# RS232_485_dsPIC30.net
KiCad netlist of a schematic drawn in Altium Designer
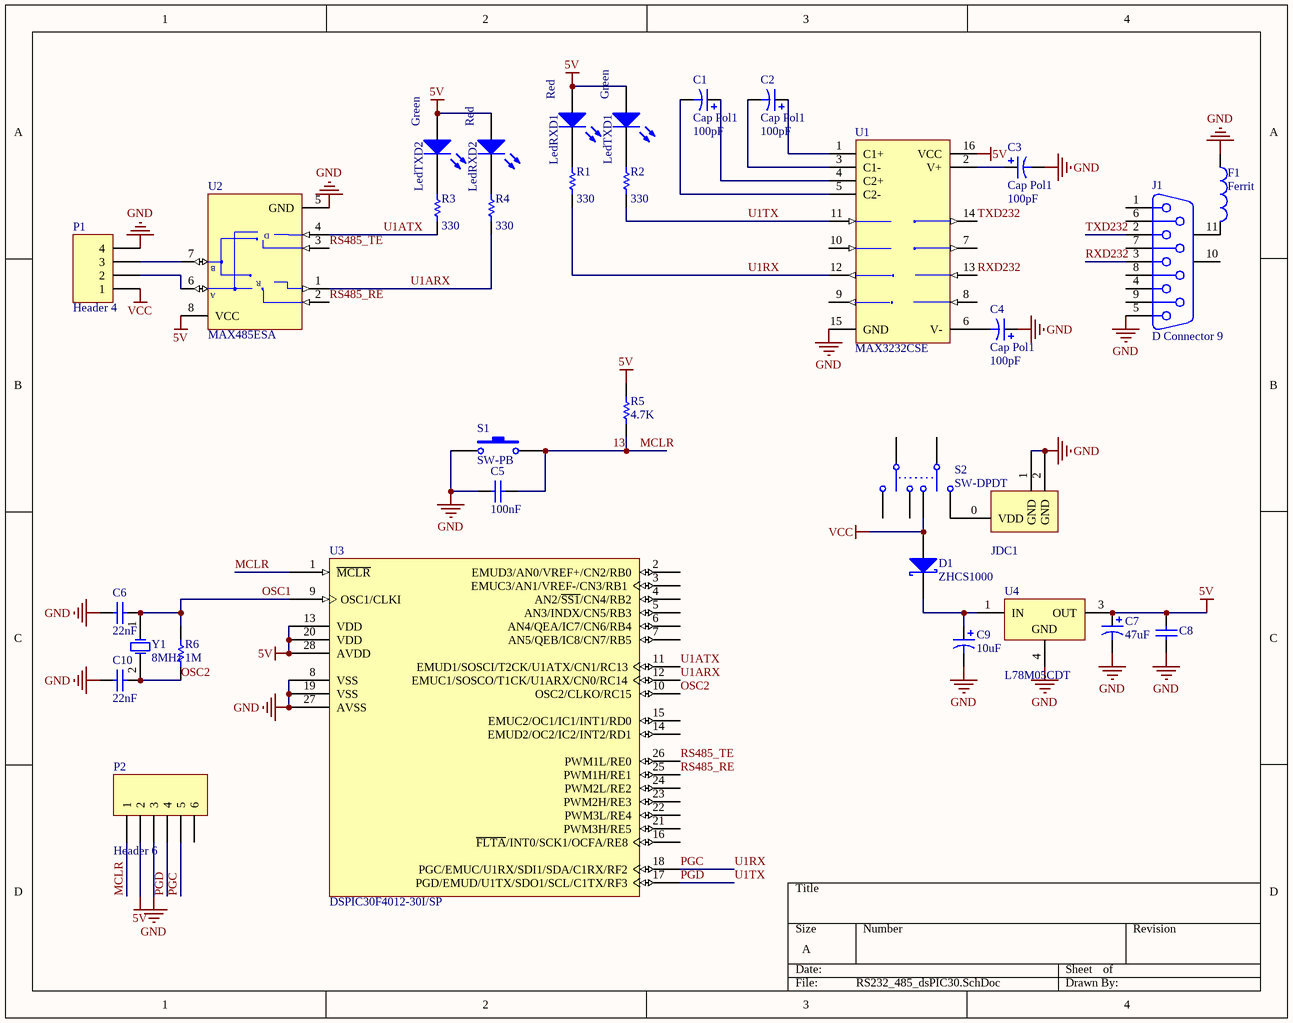
[diagram p0: RS232_485_dsPIC30.SchDoc]

(export (version "E")
  (design (tool "Eeschema 10.0.6"))
  (components
    (comp (ref "C1")
      (value "Cap Pol1")
      (footprint "CAPPR2-5x6.8")
      (description "Polarized Capacitor (Radial)")
      (fields (field (name "ALTIUM_VALUE") "100pF") (field (name "PUBLISHER") "Altium Limited"))
      (libsource (lib "Miscellaneous Devices") (part "Cap Pol1"))
    )
    (comp (ref "C2")
      (value "Cap Pol1")
      (footprint "CAPPR2-5x6.8")
      (description "Polarized Capacitor (Radial)")
      (fields (field (name "ALTIUM_VALUE") "100pF") (field (name "PUBLISHER") "Altium Limited"))
      (libsource (lib "Miscellaneous Devices") (part "Cap Pol1"))
    )
    (comp (ref "C3")
      (value "Cap Pol1")
      (footprint "CAPPR2-5x6.8")
      (description "Polarized Capacitor (Radial)")
      (fields (field (name "ALTIUM_VALUE") "100pF") (field (name "PUBLISHER") "Altium Limited"))
      (libsource (lib "Miscellaneous Devices") (part "Cap Pol1"))
    )
    (comp (ref "C4")
      (value "Cap Pol1")
      (footprint "CAPPR2-5x6.8")
      (description "Polarized Capacitor (Radial)")
      (fields (field (name "ALTIUM_VALUE") "100pF") (field (name "PUBLISHER") "Altium Limited"))
      (libsource (lib "Miscellaneous Devices") (part "Cap Pol1"))
    )
    (comp (ref "C5")
      (value "100nF")
      (footprint "CAPC1608L")
      (description "Capacitor (Semiconductor SIM Model)")
      (fields (field (name "Comment") "Cap Semi") (field (name "PUBLISHER") "Altium Limited"))
      (libsource (lib "Miscellaneous Devices") (part "Cap Semi"))
    )
    (comp (ref "C6")
      (value "22nF")
      (footprint "CAPC1608L")
      (description "Capacitor (Semiconductor SIM Model)")
      (fields (field (name "Comment") "Cap Semi") (field (name "PUBLISHER") "Altium Limited"))
      (libsource (lib "Miscellaneous Devices") (part "Cap Semi"))
    )
    (comp (ref "C7")
      (value "47uF")
      (footprint "CAP4060L")
      (description "Polarized Capacitor (Surface Mount)")
      (fields (field (name "Comment") "Cap Pol3") (field (name "PUBLISHER") "Altium Limited"))
      (libsource (lib "Miscellaneous Devices") (part "Cap Pol3"))
    )
    (comp (ref "C8")
      (value "Cap Semi")
      (footprint "CAPC1608L")
      (description "Capacitor (Semiconductor SIM Model)")
      (fields (field (name "PUBLISHER") "Altium Limited"))
      (libsource (lib "Miscellaneous Devices") (part "Cap Semi"))
    )
    (comp (ref "C9")
      (value "10uF")
      (footprint "CAPC3216L")
      (description "Polarized Capacitor (Surface Mount)")
      (fields (field (name "Comment") "Cap Pol3") (field (name "PUBLISHER") "Altium Limited"))
      (libsource (lib "Miscellaneous Devices") (part "Cap Pol3"))
    )
    (comp (ref "C10")
      (value "22nF")
      (footprint "CAPC1608L")
      (description "Capacitor (Semiconductor SIM Model)")
      (fields (field (name "Comment") "Cap Semi") (field (name "PUBLISHER") "Altium Limited"))
      (libsource (lib "Miscellaneous Devices") (part "Cap Semi"))
    )
    (comp (ref "D1")
      (value "ZHCS1000")
      (footprint "SOT95P240-3N")
      (description "Silicon AF Schottky Diode for High-Speed Switching")
      (fields (field (name "PUBLISHER") "Altium Limited"))
      (libsource (lib "Miscellaneous Devices") (part "Diode BAS70"))
    )
    (comp (ref "F1")
      (value "Ferrit")
      (footprint "INDC2012L")
      (description "Inductor")
      (fields (field (name "PUBLISHER") "Altium Limited"))
      (libsource (lib "Miscellaneous Devices") (part "Inductor"))
    )
    (comp (ref "J1")
      (value "D Connector 9")
      (footprint "DSUB1.385-2H9")
      (description "Receptacle Assembly, 9 Position, Right Angle")
      (fields (field (name "PUBLISHER") "Altium Limited"))
      (libsource (lib "Miscellaneous Connectors") (part "D Connector 9"))
    )
    (comp (ref "JDC1")
      (value "Jac_DC")
      (footprint "Jac_DC_C")
      (libsource (lib "My_Integrated_Library") (part "Jac_DC"))
    )
    (comp (ref "LedRXD1")
      (value "Red")
      (footprint "RESC2012N")
      (description "Typical RED, GREEN, YELLOW, AMBER GaAs LED")
      (fields (field (name "PUBLISHER") "Altium Limited"))
      (libsource (lib "Miscellaneous Devices") (part "LED2"))
    )
    (comp (ref "LedRXD2")
      (value "Red")
      (footprint "RESC2012N")
      (description "Typical RED, GREEN, YELLOW, AMBER GaAs LED")
      (fields (field (name "PUBLISHER") "Altium Limited"))
      (libsource (lib "Miscellaneous Devices") (part "LED2"))
    )
    (comp (ref "LedTXD1")
      (value "Green")
      (footprint "RESC2012N")
      (description "Typical RED, GREEN, YELLOW, AMBER GaAs LED")
      (fields (field (name "PUBLISHER") "Altium Limited"))
      (libsource (lib "Miscellaneous Devices") (part "LED2"))
    )
    (comp (ref "LedTXD2")
      (value "Green")
      (footprint "RESC2012N")
      (description "Typical RED, GREEN, YELLOW, AMBER GaAs LED")
      (fields (field (name "PUBLISHER") "Altium Limited"))
      (libsource (lib "Miscellaneous Devices") (part "LED2"))
    )
    (comp (ref "P1")
      (value "Header 4")
      (footprint "HEADERCN04A")
      (description "Header, 4-Pin")
      (fields (field (name "PUBLISHER") "Altium Limited"))
      (libsource (lib "Miscellaneous Connectors") (part "Header 4"))
    )
    (comp (ref "P2")
      (value "Header 6")
      (footprint "HDR1X6")
      (description "Header, 6-Pin")
      (fields (field (name "PUBLISHER") "Altium Limited"))
      (libsource (lib "Miscellaneous Connectors") (part "Header 6"))
    )
    (comp (ref "R1")
      (value "330")
      (footprint "RESC2012N")
      (description "Semiconductor Resistor")
      (fields (field (name "Comment") "Res Semi") (field (name "PUBLISHER") "Altium Limited"))
      (libsource (lib "Miscellaneous Devices") (part "Res Semi"))
    )
    (comp (ref "R2")
      (value "330")
      (footprint "RESC2012N")
      (description "Semiconductor Resistor")
      (fields (field (name "Comment") "Res Semi") (field (name "PUBLISHER") "Altium Limited"))
      (libsource (lib "Miscellaneous Devices") (part "Res Semi"))
    )
    (comp (ref "R3")
      (value "330")
      (footprint "RESC2012N")
      (description "Semiconductor Resistor")
      (fields (field (name "Comment") "Res Semi") (field (name "PUBLISHER") "Altium Limited"))
      (libsource (lib "Miscellaneous Devices") (part "Res Semi"))
    )
    (comp (ref "R4")
      (value "330")
      (footprint "RESC2012N")
      (description "Semiconductor Resistor")
      (fields (field (name "Comment") "Res Semi") (field (name "PUBLISHER") "Altium Limited"))
      (libsource (lib "Miscellaneous Devices") (part "Res Semi"))
    )
    (comp (ref "R5")
      (value "4.7K")
      (footprint "RESC2012L")
      (description "Semiconductor Resistor")
      (fields (field (name "Comment") "Res Semi") (field (name "PUBLISHER") "Altium Limited"))
      (libsource (lib "Miscellaneous Devices") (part "Res Semi"))
    )
    (comp (ref "R6")
      (value "1M")
      (footprint "RESC2012L")
      (description "Semiconductor Resistor")
      (fields (field (name "Comment") "Res Semi") (field (name "PUBLISHER") "Altium Limited"))
      (libsource (lib "Miscellaneous Devices") (part "Res Semi"))
    )
    (comp (ref "S1")
      (value "SW-PB")
      (footprint "SPST-2")
      (description "Switch")
      (fields (field (name "PUBLISHER") "Altium Limited"))
      (libsource (lib "Miscellaneous Devices") (part "SW-PB"))
    )
    (comp (ref "S2")
      (value "SW-DPDT")
      (footprint "DPDT-6")
      (description "Double-Pole, Double-Throw Switch")
      (fields (field (name "PUBLISHER") "Altium Limited"))
      (libsource (lib "Miscellaneous Devices") (part "SW-DPDT"))
    )
    (comp (ref "U1")
      (value "MAX3232CSE")
      (footprint "JE16")
      (description "3.0V TO 5.5V, Low-Power, up to 1Mbps, True RS-232 Transceiver Using Four 0.1µF External Capacitor")
      (fields (field (name "PUBLISHER") "Altium Limited"))
      (libsource (lib "Maxim Communication Transceiver") (part "MAX3232CSE"))
    )
    (comp (ref "U2")
      (value "MAX485ESA")
      (footprint "JA8A")
      (description "Low-Power, Slew-Rate-Limited RS-485/RS-422 Transceiver")
      (fields (field (name "PUBLISHER") "Altium Limited"))
      (libsource (lib "Maxim Communication Transceiver") (part "MAX485ESA"))
    )
    (comp (ref "U3")
      (value "DSPIC30F4012-30I/SP")
      (footprint "SPDIP300-SP28")
      (fields (field (name "PUBLISHER") "Altium Limited"))
      (libsource (lib "Microchip DSC 16-Bit dsPIC30F") (part "DSPIC30F4012-30I/SP"))
    )
    (comp (ref "U4")
      (value "L78M05CDT")
      (footprint "ST-Microelectronics Footprints:TO-252")
      (description "Positive Voltage Regulator")
      (fields (field (name "PUBLISHER") "Altium Limited"))
      (libsource (lib "ST Power Mgt Voltage Regulator") (part "L78M05CDT"))
    )
    (comp (ref "Y1")
      (value "8MHz")
      (footprint "RAD-0.2")
      (description "Crystal Oscillator")
      (fields (field (name "PUBLISHER") "Altium Limited"))
      (libsource (lib "Miscellaneous Devices") (part "XTAL"))
    )
  )
  (nets
    (net (code "1") (name "/13") (class "Default")
      (node (ref "C5") (pin "2") (pinfunction "2_2") (pintype "passive"))
      (node (ref "P2") (pin "1") (pinfunction "1_1") (pintype "passive"))
      (node (ref "R5") (pin "1") (pinfunction "1_1") (pintype "passive"))
      (node (ref "S1") (pin "2") (pinfunction "2_2") (pintype "passive"))
      (node (ref "U3") (pin "1") (pinfunction "~{MCLR}_1") (pintype "input"))
    )
    (net (code "2") (name "/OSC1") (class "Default")
      (node (ref "C6") (pin "2") (pinfunction "2_2") (pintype "passive"))
      (node (ref "R6") (pin "1") (pinfunction "1_1") (pintype "passive"))
      (node (ref "U3") (pin "9") (pinfunction "OSC1/CLKI_9") (pintype "input"))
      (node (ref "Y1") (pin "1") (pinfunction "OSC1_1") (pintype "passive"))
    )
    (net (code "3") (name "/OSC2") (class "Default")
      (node (ref "C10") (pin "2") (pinfunction "2_2") (pintype "passive"))
      (node (ref "R6") (pin "2") (pinfunction "2_2") (pintype "passive"))
      (node (ref "U3") (pin "10") (pinfunction "OSC2/CLKO/RC15_10") (pintype "bidirectional"))
      (node (ref "Y1") (pin "2") (pinfunction "OSC2_2") (pintype "passive"))
    )
    (net (code "4") (name "/PGC") (class "Default")
      (node (ref "P2") (pin "5") (pinfunction "5_5") (pintype "passive"))
      (node (ref "R1") (pin "2") (pinfunction "2_2") (pintype "passive"))
      (node (ref "U1") (pin "12") (pinfunction "R1OUT_12") (pintype "output"))
      (node (ref "U3") (pin "18") (pinfunction "PGC/EMUC/U1RX/SDI1/SDA/C1RX/RF2_18") (pintype "bidirectional"))
    )
    (net (code "5") (name "/PGD") (class "Default")
      (node (ref "P2") (pin "4") (pinfunction "4_4") (pintype "passive"))
      (node (ref "R2") (pin "2") (pinfunction "2_2") (pintype "passive"))
      (node (ref "U1") (pin "11") (pinfunction "T1IN_11") (pintype "input"))
      (node (ref "U3") (pin "17") (pinfunction "PGD/EMUD/U1TX/SDO1/SCL/C1TX/RF3_17") (pintype "bidirectional"))
    )
    (net (code "6") (name "/RS485_RE") (class "Default")
      (node (ref "U2") (pin "2") (pinfunction "~{RE}_2") (pintype "input"))
      (node (ref "U3") (pin "25") (pinfunction "PWM1H/RE1_25") (pintype "bidirectional"))
    )
    (net (code "7") (name "/RS485_TE") (class "Default")
      (node (ref "U2") (pin "3") (pinfunction "DE_3") (pintype "input"))
      (node (ref "U3") (pin "26") (pinfunction "PWM1L/RE0_26") (pintype "bidirectional"))
    )
    (net (code "8") (name "/RXD232") (class "Default")
      (node (ref "J1") (pin "3") (pinfunction "3_3") (pintype "passive"))
      (node (ref "U1") (pin "13") (pinfunction "R1IN_13") (pintype "input"))
    )
    (net (code "9") (name "/TXD232") (class "Default")
      (node (ref "J1") (pin "2") (pinfunction "2_2") (pintype "passive"))
      (node (ref "U1") (pin "14") (pinfunction "T1OUT_14") (pintype "output"))
    )
    (net (code "10") (name "/U1ARX") (class "Default")
      (node (ref "R4") (pin "2") (pinfunction "2_2") (pintype "passive"))
      (node (ref "U2") (pin "1") (pinfunction "RO_1") (pintype "output"))
      (node (ref "U3") (pin "12") (pinfunction "EMUC1/SOSCO/T1CK/U1ARX/CN0/RC14_12") (pintype "bidirectional"))
    )
    (net (code "11") (name "/U1ATX") (class "Default")
      (node (ref "R3") (pin "2") (pinfunction "2_2") (pintype "passive"))
      (node (ref "U2") (pin "4") (pinfunction "DI_4") (pintype "input"))
      (node (ref "U3") (pin "11") (pinfunction "EMUD1/SOSCI/T2CK/U1ATX/CN1/RC13_11") (pintype "bidirectional"))
    )
    (net (code "12") (name "5V") (class "Default")
      (node (ref "C7") (pin "1") (pinfunction "1_1") (pintype "passive"))
      (node (ref "C8") (pin "2") (pinfunction "2_2") (pintype "passive"))
      (node (ref "LedRXD1") (pin "1") (pinfunction "A_1") (pintype "passive"))
      (node (ref "LedRXD2") (pin "1") (pinfunction "A_1") (pintype "passive"))
      (node (ref "LedTXD1") (pin "1") (pinfunction "A_1") (pintype "passive"))
      (node (ref "LedTXD2") (pin "1") (pinfunction "A_1") (pintype "passive"))
      (node (ref "P2") (pin "2") (pinfunction "2_2") (pintype "passive"))
      (node (ref "R5") (pin "2") (pinfunction "2_2") (pintype "passive"))
      (node (ref "U1") (pin "16") (pinfunction "VCC_16") (pintype "power_in"))
      (node (ref "U2") (pin "8") (pinfunction "VCC_8") (pintype "power_in"))
      (node (ref "U3") (pin "13") (pinfunction "VDD_13") (pintype "power_in"))
      (node (ref "U3") (pin "20") (pinfunction "VDD_20") (pintype "power_in"))
      (node (ref "U3") (pin "28") (pinfunction "AVDD_28") (pintype "power_in"))
      (node (ref "U4") (pin "3") (pinfunction "OUT_3") (pintype "power_in"))
    )
    (net (code "13") (name "GND") (class "Default")
      (node (ref "C10") (pin "1") (pinfunction "1_1") (pintype "passive"))
      (node (ref "C3") (pin "2") (pinfunction "2_2") (pintype "passive"))
      (node (ref "C4") (pin "1") (pinfunction "1_1") (pintype "passive"))
      (node (ref "C5") (pin "1") (pinfunction "1_1") (pintype "passive"))
      (node (ref "C6") (pin "1") (pinfunction "1_1") (pintype "passive"))
      (node (ref "C7") (pin "2") (pinfunction "2_2") (pintype "passive"))
      (node (ref "C8") (pin "1") (pinfunction "1_1") (pintype "passive"))
      (node (ref "C9") (pin "2") (pinfunction "2_2") (pintype "passive"))
      (node (ref "F1") (pin "1") (pinfunction "1_1") (pintype "passive"))
      (node (ref "J1") (pin "5") (pinfunction "5_5") (pintype "passive"))
      (node (ref "JDC1") (pin "1") (pinfunction "GND_1") (pintype "power_in"))
      (node (ref "JDC1") (pin "2") (pinfunction "GND_2") (pintype "power_in"))
      (node (ref "P1") (pin "4") (pinfunction "4_4") (pintype "passive"))
      (node (ref "P2") (pin "3") (pinfunction "3_3") (pintype "passive"))
      (node (ref "S1") (pin "1") (pinfunction "1_1") (pintype "passive"))
      (node (ref "U1") (pin "15") (pinfunction "GND_15") (pintype "power_in"))
      (node (ref "U2") (pin "5") (pinfunction "GND_5") (pintype "power_in"))
      (node (ref "U3") (pin "19") (pinfunction "VSS_19") (pintype "power_in"))
      (node (ref "U3") (pin "27") (pinfunction "AVSS_27") (pintype "power_in"))
      (node (ref "U3") (pin "8") (pinfunction "VSS_8") (pintype "power_in"))
      (node (ref "U4") (pin "4") (pinfunction "GND_4") (pintype "power_in"))
    )
    (net (code "14") (name "Net-(D1-K)") (class "Default")
      (node (ref "C9") (pin "1") (pinfunction "1_1") (pintype "passive"))
      (node (ref "D1") (pin "3") (pinfunction "K_3") (pintype "passive"))
      (node (ref "U4") (pin "1") (pinfunction "IN_1") (pintype "power_in"))
    )
    (net (code "15") (name "Net-(J1-MH2)") (class "Default")
      (node (ref "F1") (pin "2") (pinfunction "2_2") (pintype "passive"))
      (node (ref "J1") (pin "11") (pinfunction "MH2_11") (pintype "passive"))
    )
    (net (code "16") (name "Net-(JDC1-VDD)") (class "Default")
      (node (ref "JDC1") (pin "0") (pinfunction "VDD_0") (pintype "power_in"))
      (node (ref "S2") (pin "2") (pinfunction "2_2") (pintype "passive"))
    )
    (net (code "17") (name "Net-(LedRXD1-K)") (class "Default")
      (node (ref "LedRXD1") (pin "2") (pinfunction "K_2") (pintype "passive"))
      (node (ref "R1") (pin "1") (pinfunction "1_1") (pintype "passive"))
    )
    (net (code "18") (name "Net-(LedRXD2-K)") (class "Default")
      (node (ref "LedRXD2") (pin "2") (pinfunction "K_2") (pintype "passive"))
      (node (ref "R4") (pin "1") (pinfunction "1_1") (pintype "passive"))
    )
    (net (code "19") (name "Net-(LedTXD1-K)") (class "Default")
      (node (ref "LedTXD1") (pin "2") (pinfunction "K_2") (pintype "passive"))
      (node (ref "R2") (pin "1") (pinfunction "1_1") (pintype "passive"))
    )
    (net (code "20") (name "Net-(LedTXD2-K)") (class "Default")
      (node (ref "LedTXD2") (pin "2") (pinfunction "K_2") (pintype "passive"))
      (node (ref "R3") (pin "1") (pinfunction "1_1") (pintype "passive"))
    )
    (net (code "21") (name "Net-(U1-C1+)") (class "Default")
      (node (ref "C2") (pin "1") (pinfunction "1_1") (pintype "passive"))
      (node (ref "U1") (pin "1") (pinfunction "C1+_1") (pintype "passive"))
    )
    (net (code "22") (name "Net-(U1-C1-)") (class "Default")
      (node (ref "C2") (pin "2") (pinfunction "2_2") (pintype "passive"))
      (node (ref "U1") (pin "3") (pinfunction "C1-_3") (pintype "passive"))
    )
    (net (code "23") (name "Net-(U1-C2+)") (class "Default")
      (node (ref "C1") (pin "1") (pinfunction "1_1") (pintype "passive"))
      (node (ref "U1") (pin "4") (pinfunction "C2+_4") (pintype "passive"))
    )
    (net (code "24") (name "Net-(U1-C2-)") (class "Default")
      (node (ref "C1") (pin "2") (pinfunction "2_2") (pintype "passive"))
      (node (ref "U1") (pin "5") (pinfunction "C2-_5") (pintype "passive"))
    )
    (net (code "25") (name "Net-(U1-V+)") (class "Default")
      (node (ref "C3") (pin "1") (pinfunction "1_1") (pintype "passive"))
      (node (ref "U1") (pin "2") (pinfunction "V+_2") (pintype "power_in"))
    )
    (net (code "26") (name "Net-(U1-V-)") (class "Default")
      (node (ref "C4") (pin "2") (pinfunction "2_2") (pintype "passive"))
      (node (ref "U1") (pin "6") (pinfunction "V-_6") (pintype "power_in"))
    )
    (net (code "27") (name "Net-(U2-A)") (class "Default")
      (node (ref "P1") (pin "2") (pinfunction "2_2") (pintype "passive"))
      (node (ref "U2") (pin "6") (pinfunction "A_6") (pintype "bidirectional"))
    )
    (net (code "28") (name "Net-(U2-B)") (class "Default")
      (node (ref "P1") (pin "3") (pinfunction "3_3") (pintype "passive"))
      (node (ref "U2") (pin "7") (pinfunction "B_7") (pintype "bidirectional"))
    )
    (net (code "29") (name "VCC") (class "Default")
      (node (ref "D1") (pin "1") (pinfunction "A_1") (pintype "passive"))
      (node (ref "P1") (pin "1") (pinfunction "1_1") (pintype "passive"))
      (node (ref "S2") (pin "3") (pinfunction "3_3") (pintype "passive"))
    )
    (net (code "30") (name "unconnected-(J1-MH1-Pad10)") (class "Default")
      (node (ref "J1") (pin "10") (pinfunction "MH1_10") (pintype "passive"))
    )
    (net (code "31") (name "unconnected-(J1-Pad1)") (class "Default")
      (node (ref "J1") (pin "1") (pinfunction "1_1") (pintype "passive"))
    )
    (net (code "32") (name "unconnected-(J1-Pad4)") (class "Default")
      (node (ref "J1") (pin "4") (pinfunction "4_4") (pintype "passive"))
    )
    (net (code "33") (name "unconnected-(J1-Pad6)") (class "Default")
      (node (ref "J1") (pin "6") (pinfunction "6_6") (pintype "passive"))
    )
    (net (code "34") (name "unconnected-(J1-Pad7)") (class "Default")
      (node (ref "J1") (pin "7") (pinfunction "7_7") (pintype "passive"))
    )
    (net (code "35") (name "unconnected-(J1-Pad8)") (class "Default")
      (node (ref "J1") (pin "8") (pinfunction "8_8") (pintype "passive"))
    )
    (net (code "36") (name "unconnected-(J1-Pad9)") (class "Default")
      (node (ref "J1") (pin "9") (pinfunction "9_9") (pintype "passive"))
    )
    (net (code "37") (name "unconnected-(P2-Pad6)") (class "Default")
      (node (ref "P2") (pin "6") (pinfunction "6_6") (pintype "passive"))
    )
    (net (code "38") (name "unconnected-(S2-Pad1)") (class "Default")
      (node (ref "S2") (pin "1") (pinfunction "1_1") (pintype "passive"))
    )
    (net (code "39") (name "unconnected-(S2-Pad4)") (class "Default")
      (node (ref "S2") (pin "4") (pinfunction "4_4") (pintype "passive"))
    )
    (net (code "40") (name "unconnected-(S2-Pad5)") (class "Default")
      (node (ref "S2") (pin "5") (pinfunction "5_5") (pintype "passive"))
    )
    (net (code "41") (name "unconnected-(S2-Pad6)") (class "Default")
      (node (ref "S2") (pin "6") (pinfunction "6_6") (pintype "passive"))
    )
    (net (code "42") (name "unconnected-(U1-R2IN-Pad8)") (class "Default")
      (node (ref "U1") (pin "8") (pinfunction "R2IN_8") (pintype "input"))
    )
    (net (code "43") (name "unconnected-(U1-R2OUT-Pad9)") (class "Default")
      (node (ref "U1") (pin "9") (pinfunction "R2OUT_9") (pintype "output"))
    )
    (net (code "44") (name "unconnected-(U1-T2IN-Pad10)") (class "Default")
      (node (ref "U1") (pin "10") (pinfunction "T2IN_10") (pintype "input"))
    )
    (net (code "45") (name "unconnected-(U1-T2OUT-Pad7)") (class "Default")
      (node (ref "U1") (pin "7") (pinfunction "T2OUT_7") (pintype "output"))
    )
    (net (code "46") (name "unconnected-(U3-AN2{slash}~{SS1}{slash}CN4{slash}RB2-Pad4)") (class "Default")
      (node (ref "U3") (pin "4") (pinfunction "AN2/~{SS1}/CN4/RB2_4") (pintype "bidirectional"))
    )
    (net (code "47") (name "unconnected-(U3-AN3{slash}INDX{slash}CN5{slash}RB3-Pad5)") (class "Default")
      (node (ref "U3") (pin "5") (pinfunction "AN3/INDX/CN5/RB3_5") (pintype "bidirectional"))
    )
    (net (code "48") (name "unconnected-(U3-AN4{slash}QEA{slash}IC7{slash}CN6{slash}RB4-Pad6)") (class "Default")
      (node (ref "U3") (pin "6") (pinfunction "AN4/QEA/IC7/CN6/RB4_6") (pintype "bidirectional"))
    )
    (net (code "49") (name "unconnected-(U3-AN5{slash}QEB{slash}IC8{slash}CN7{slash}RB5-Pad7)") (class "Default")
      (node (ref "U3") (pin "7") (pinfunction "AN5/QEB/IC8/CN7/RB5_7") (pintype "bidirectional"))
    )
    (net (code "50") (name "unconnected-(U3-EMUC2{slash}OC1{slash}IC1{slash}INT1{slash}RD0-Pad15)") (class "Default")
      (node (ref "U3") (pin "15") (pinfunction "EMUC2/OC1/IC1/INT1/RD0_15") (pintype "bidirectional"))
    )
    (net (code "51") (name "unconnected-(U3-EMUC3{slash}AN1{slash}VREF-{slash}CN3{slash}RB1-Pad3)") (class "Default")
      (node (ref "U3") (pin "3") (pinfunction "EMUC3/AN1/VREF-/CN3/RB1_3") (pintype "bidirectional"))
    )
    (net (code "52") (name "unconnected-(U3-EMUD2{slash}OC2{slash}IC2{slash}INT2{slash}RD1-Pad14)") (class "Default")
      (node (ref "U3") (pin "14") (pinfunction "EMUD2/OC2/IC2/INT2/RD1_14") (pintype "bidirectional"))
    )
    (net (code "53") (name "unconnected-(U3-EMUD3{slash}AN0{slash}VREF+{slash}CN2{slash}RB0-Pad2)") (class "Default")
      (node (ref "U3") (pin "2") (pinfunction "EMUD3/AN0/VREF+/CN2/RB0_2") (pintype "bidirectional"))
    )
    (net (code "54") (name "unconnected-(U3-PWM2H{slash}RE3-Pad23)") (class "Default")
      (node (ref "U3") (pin "23") (pinfunction "PWM2H/RE3_23") (pintype "bidirectional"))
    )
    (net (code "55") (name "unconnected-(U3-PWM2L{slash}RE2-Pad24)") (class "Default")
      (node (ref "U3") (pin "24") (pinfunction "PWM2L/RE2_24") (pintype "bidirectional"))
    )
    (net (code "56") (name "unconnected-(U3-PWM3H{slash}RE5-Pad21)") (class "Default")
      (node (ref "U3") (pin "21") (pinfunction "PWM3H/RE5_21") (pintype "bidirectional"))
    )
    (net (code "57") (name "unconnected-(U3-PWM3L{slash}RE4-Pad22)") (class "Default")
      (node (ref "U3") (pin "22") (pinfunction "PWM3L/RE4_22") (pintype "bidirectional"))
    )
    (net (code "58") (name "unconnected-(U3-~{FLTA}{slash}INT0{slash}SCK1{slash}OCFA{slash}RE8-Pad16)") (class "Default")
      (node (ref "U3") (pin "16") (pinfunction "~{FLTA}/INT0/SCK1/OCFA/RE8_16") (pintype "bidirectional"))
    )
  )
)
